# H1DR21.net
KiCad netlist of a schematic drawn in EAGLE
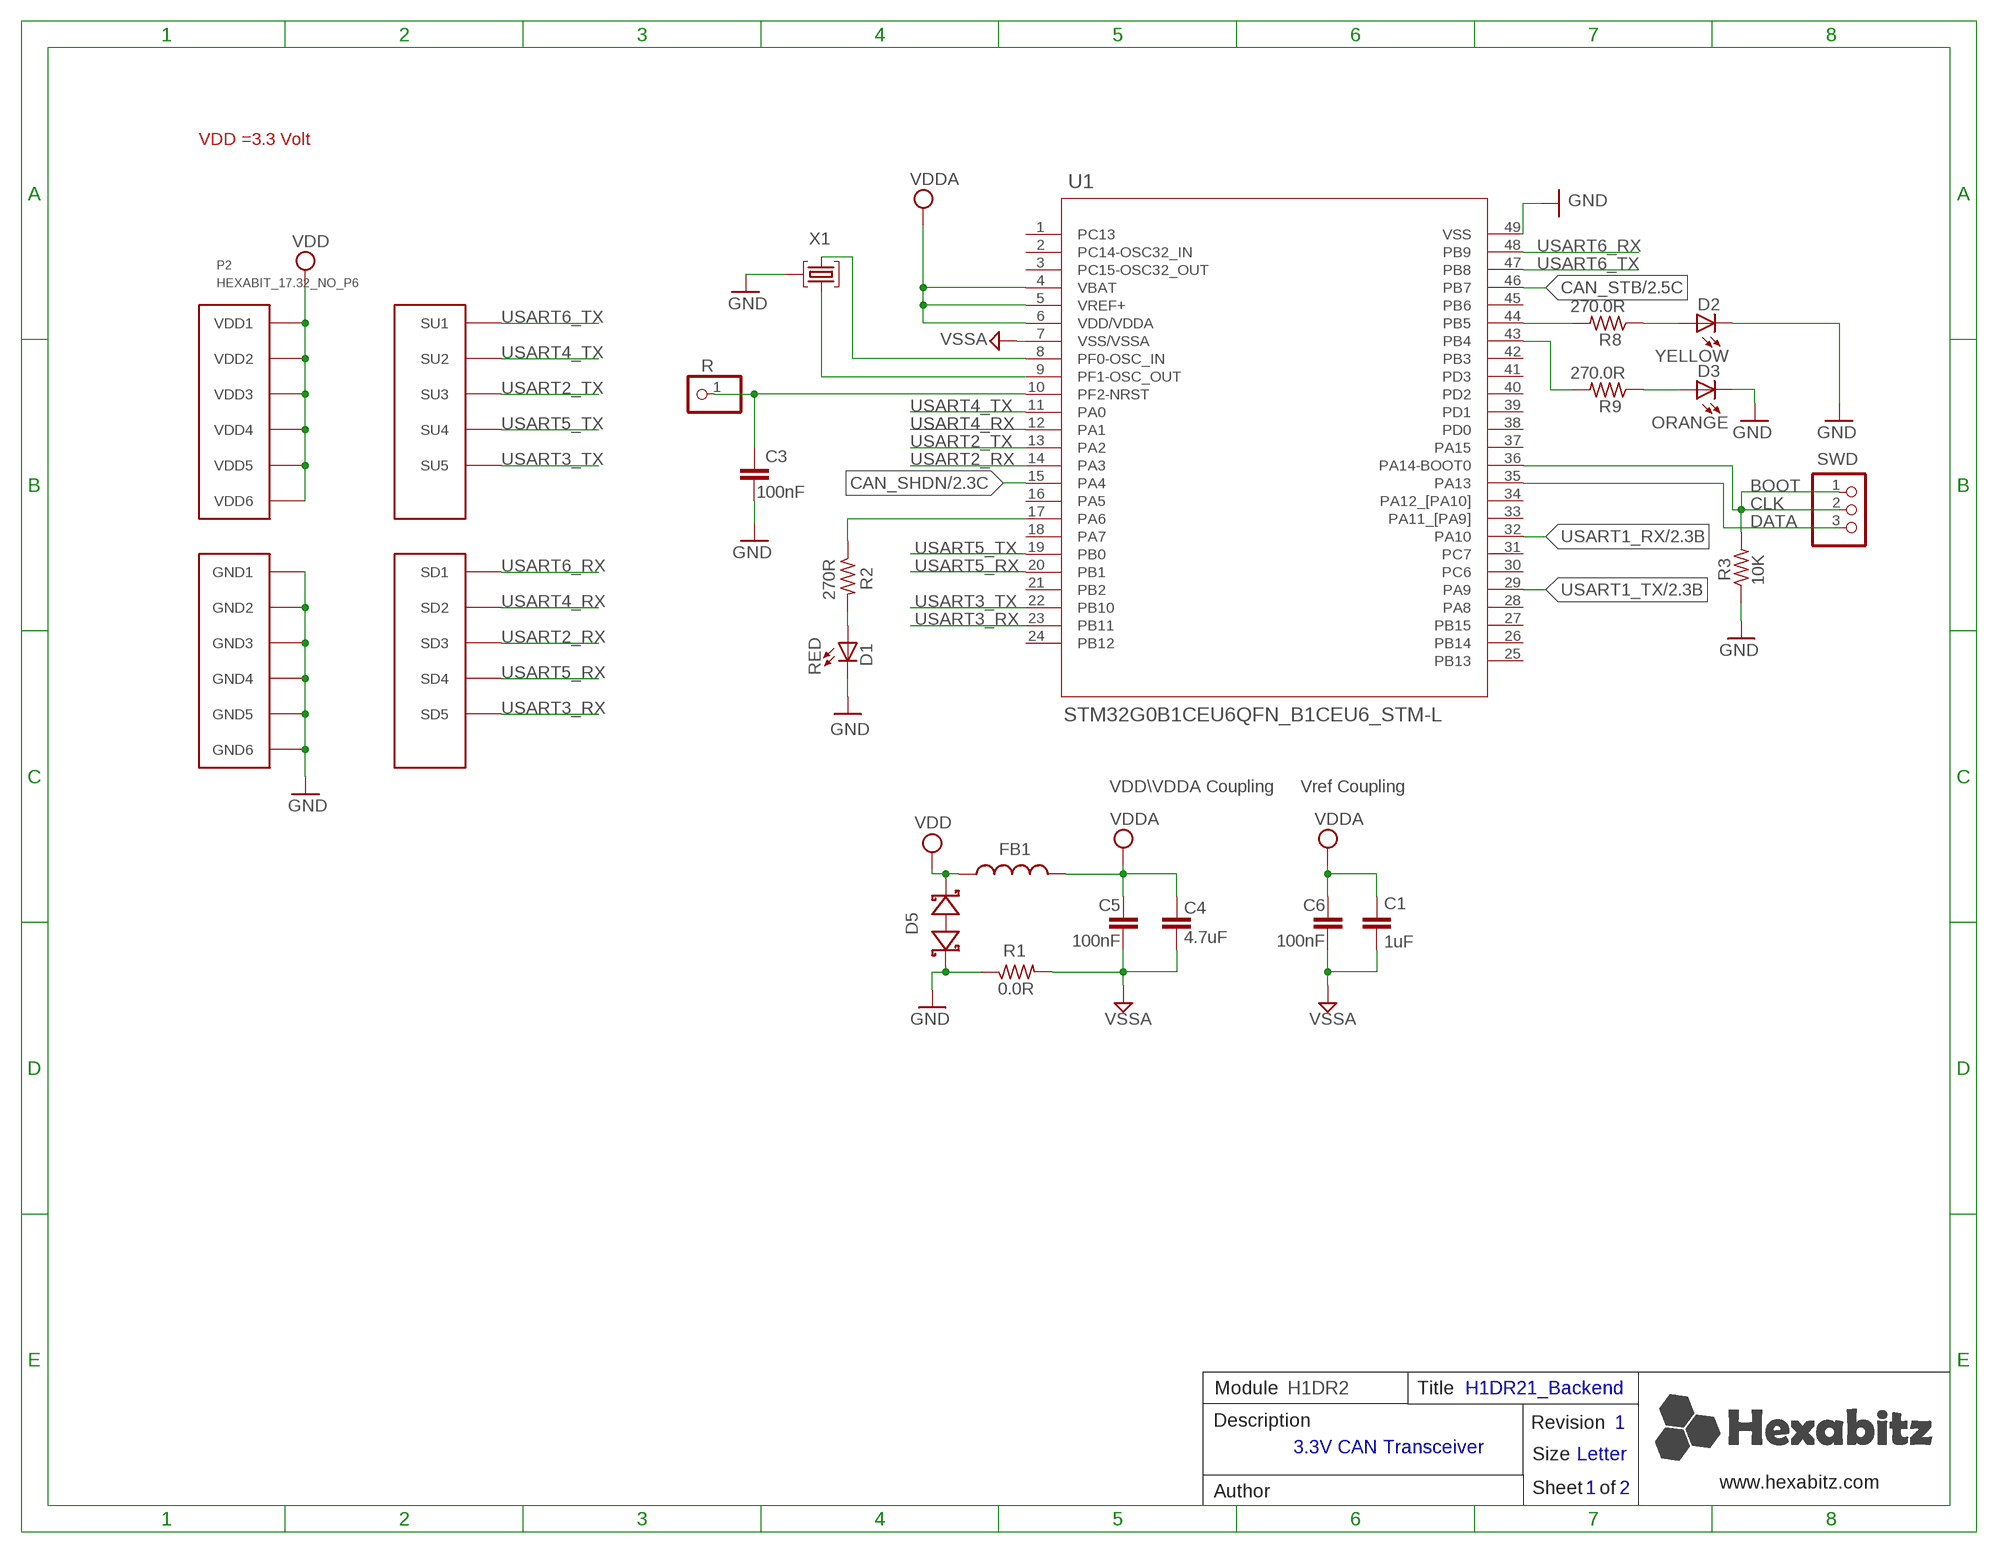
[diagram p0: schematic, sheet 1]
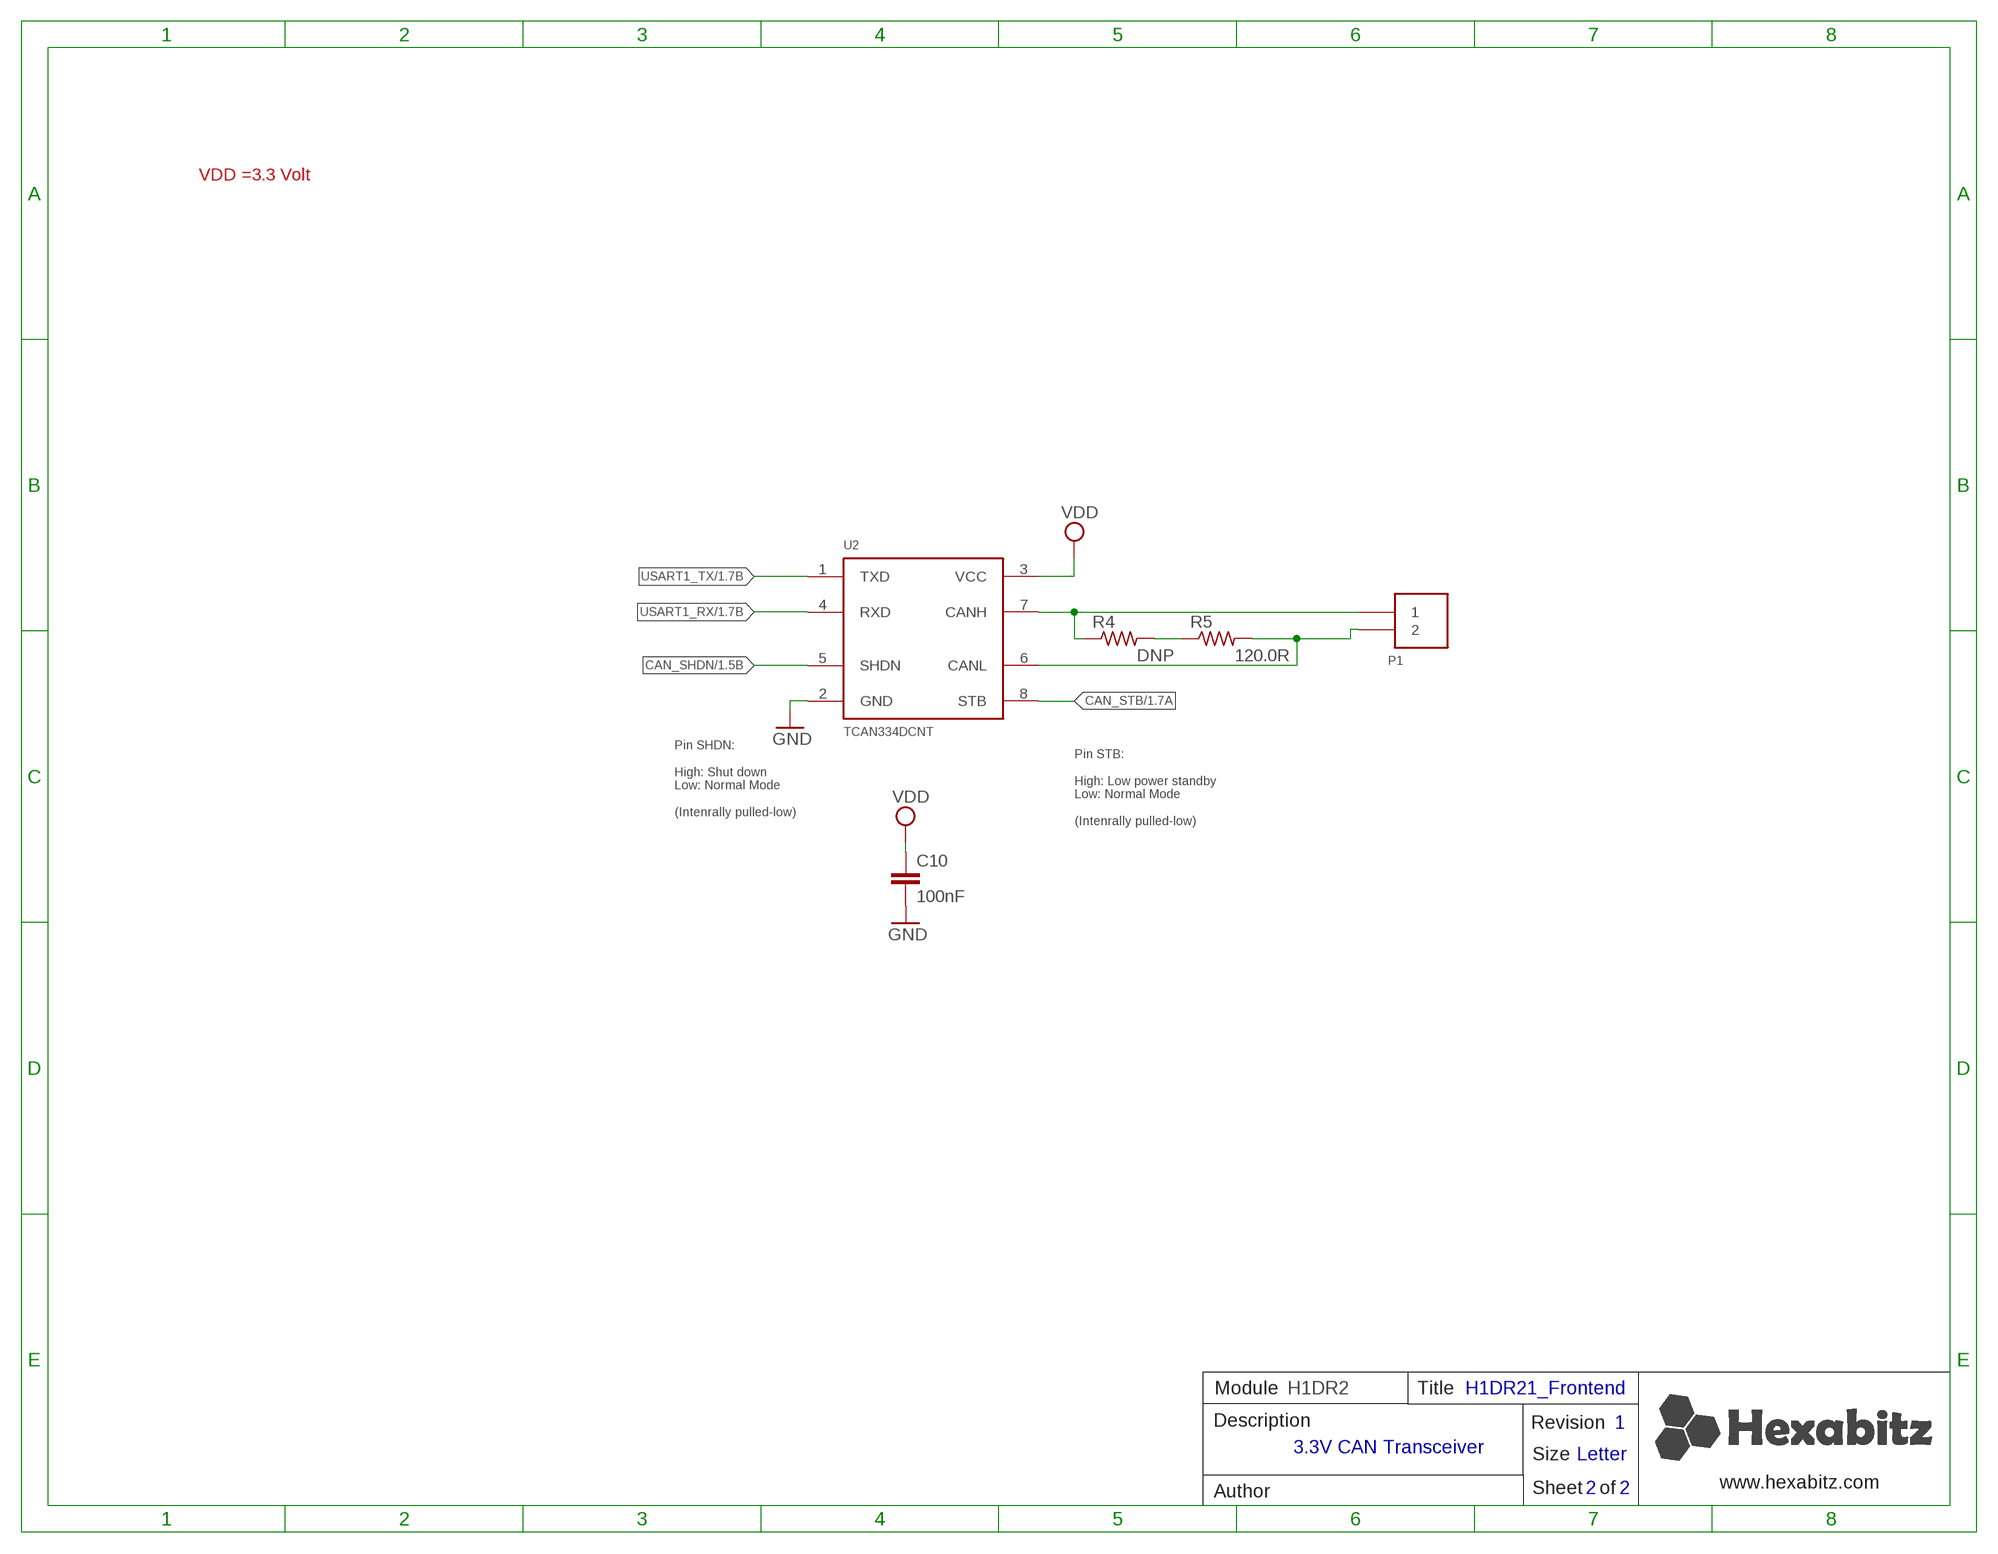
[diagram p1: schematic, sheet 2]

(export (version "E")
  (design (tool "Eeschema 10.0.6"))
  (components
    (comp (ref "C10")
      (value "100nF")
      (footprint "eagle-import:C-0603")
      (fields
        (field (name "CAPACITANCE") "100nF")
        (field (name "MFN") "KEMET")
        (field (name "MPN") "C0603C104K8RACTU")
        (field (name "OCTOPART_URL") "https://octopart.com/c0603c104k8ractu-kemet-145075?r=sp&s=9bS9ASSwSEqMCE9KBEQZ0g")
        (field (name "TOLERANCE") "10%")
        (field (name "VOLTAGE_RATING") "10V")
      )
      (libsource (lib "eagle-import") (part "Hexabitz_C-0603"))
    )
    (comp (ref "P1")
      (value "1546111-2")
      (footprint "eagle-import:1546111-2")
      (libsource (lib "eagle-import") (part "1546111-2"))
    )
    (comp (ref "R4")
      (value "DNP")
      (footprint "eagle-import:R-0603")
      (fields
        (field (name "MFN") "Yageo")
        (field (name "MPN") "RC0603JR-070RL")
        (field (name "OCTOPART_URL") "https://octopart.com/search?q=RC0603JR-070RL")
        (field (name "RESISTANCE") "0.0 Ohm")
      )
      (libsource (lib "eagle-import") (part "Hexabitz_R-0603"))
    )
    (comp (ref "R5")
      (value "120.0R")
      (footprint "eagle-import:R-0603")
      (fields
        (field (name "MFN") "Yageo")
        (field (name "MPN") "AC0603FR-07120RL")
        (field (name "OCTOPART_URL") "https://octopart.com/search?q=AC0603FR-07120RL&start=0")
        (field (name "RESISTANCE") "120.0 Ohm")
        (field (name "TOLERANCE") "1%")
      )
      (libsource (lib "eagle-import") (part "Hexabitz_R-0603"))
    )
    (comp (ref "U2")
      (value "TCAN334DCNT")
      (footprint "eagle-import:TCAN334DCNT")
      (libsource (lib "eagle-import") (part "TCAN334DCNT"))
    )
    (comp (ref "C1")
      (value "1uF")
      (footprint "eagle-import:C-0805")
      (libsource (lib "eagle-import") (part "C-0805"))
    )
    (comp (ref "C3")
      (value "100nF")
      (footprint "eagle-import:C-0603")
      (libsource (lib "eagle-import") (part "C-0603"))
    )
    (comp (ref "C4")
      (value "4.7uF")
      (footprint "eagle-import:C-0805")
      (libsource (lib "eagle-import") (part "C-0805"))
    )
    (comp (ref "C5")
      (value "100nF")
      (footprint "eagle-import:C-0603")
      (libsource (lib "eagle-import") (part "C-0603"))
    )
    (comp (ref "C6")
      (value "100nF")
      (footprint "eagle-import:C-0603")
      (libsource (lib "eagle-import") (part "C-0603"))
    )
    (comp (ref "D1")
      (value "RED")
      (footprint "eagle-import:VLMS1300-GS08")
      (fields
        (field (name "MPN") "VLMS1300-GS08")
        (field (name "MFN") "Vishay")
        (field (name "MPN_1") "VLMS1300-GS08")
        (field (name "OCTOPART_URL") "https://octopart.com/vlms1300-gs08-vishay-21709201?r=sp&s=_gcP4_q8T1SC6PJQPTQ9yA")
      )
      (libsource (lib "eagle-import") (part "VLMS1300-GS08"))
    )
    (comp (ref "D2")
      (value "YELLOW")
      (footprint "eagle-import:VLMS1300-GS08")
      (fields
        (field (name "MPN") "VLMS1300-GS08")
        (field (name "OCTOPART_URL") "https://octopart.com/vlms1300-gs08-vishay-21709201?r=sp&s=_gcP4_q8T1SC6PJQPTQ9yA")
      )
      (libsource (lib "eagle-import") (part "VLMS1300-GS08"))
    )
    (comp (ref "D3")
      (value "ORANGE")
      (footprint "eagle-import:VLMS1300-GS08")
      (fields
        (field (name "MPN") "VLMS1300-GS08")
        (field (name "OCTOPART_URL") "https://octopart.com/vlms1300-gs08-vishay-21709201?r=sp&s=_gcP4_q8T1SC6PJQPTQ9yA")
      )
      (libsource (lib "eagle-import") (part "VLMS1300-GS08"))
    )
    (comp (ref "D5")
      (value "BOURNS_CDSOD323-T03SCBOURNS_CDSOD323-T03SC_0_0")
      (footprint "eagle-import:BOURNS_CDSOD323-T03SC_0")
      (fields (field (name "MPN") "CDSOD323-T03SC"))
      (libsource (lib "eagle-import") (part "BOURNS_CDSOD323-T03SCBOURNS_CDSOD323-T03SC_0_0"))
    )
    (comp (ref "FB1")
      (value "FB-TDK_MMZ1608Y300B")
      (footprint "eagle-import:FB-0603")
      (fields
        (field (name "MFN") "TDK ")
        (field (name "MPN") "MMZ1608Y300B")
        (field (name "OCTOPART_URL") "https://octopart.com/mmz1608y300b-tdk-368280?r=sp&s=cd9_2ZEqQ9q9UNBuQgHAiA")
      )
      (libsource (lib "eagle-import") (part "FB-0603"))
    )
    (comp (ref "P2")
      (value "HEXABIT_17.32_NO_P6")
      (footprint "eagle-import:HEXABIT_17.32_NO_P6")
      (libsource (lib "eagle-import") (part "HEXABIT_?_NO_P617.32"))
    )
    (comp (ref "R")
      (value "R")
      (footprint "eagle-import:1X01")
      (fields (field (name "MPN") "87227-1"))
      (libsource (lib "eagle-import") (part "PINHD-1X1"))
    )
    (comp (ref "R1")
      (value "0.0R")
      (footprint "eagle-import:R-0603")
      (fields
        (field (name "MFN") "Yageo")
        (field (name "MPN") "RC0603JR-070RL")
        (field (name "OCTOPART_URL") "https://octopart.com/rc0603jr-070rl-yageo-1241539?r=sp&s=X2NteqRjRNWrnx42Y0aliA")
        (field (name "RESISTANCE") "0.0 Ohm")
      )
      (libsource (lib "eagle-import") (part "R-0603"))
    )
    (comp (ref "R2")
      (value "270R")
      (footprint "eagle-import:R-0603")
      (libsource (lib "eagle-import") (part "R-0603"))
    )
    (comp (ref "R3")
      (value "10K")
      (footprint "eagle-import:R-0603")
      (libsource (lib "eagle-import") (part "R-0603"))
    )
    (comp (ref "R8")
      (value "270.0R")
      (footprint "eagle-import:R-0603")
      (libsource (lib "eagle-import") (part "R-0603"))
    )
    (comp (ref "R9")
      (value "270.0R")
      (footprint "eagle-import:R-0603")
      (libsource (lib "eagle-import") (part "R-0603"))
    )
    (comp (ref "SWD")
      (value "PINHD-1X3")
      (footprint "eagle-import:1X03")
      (libsource (lib "eagle-import") (part "PINHD-1X3"))
    )
    (comp (ref "U1")
      (value "STM32G0B1CEU6QFN_B1CEU6_STM-L")
      (footprint "eagle-import:QFN_B1CEU6_STM-L")
      (fields
        (field (name "MANUFACTURER_PART_NUMBER") "STM32G0B1CEU6")
        (field (name "SPICEPREFIX") "X")
        (field (name "COPYRIGHT") "Copyright (C) 2021 Ultra Librarian. All rights reserved.")
      )
      (libsource (lib "eagle-import") (part "STM32G0B1CEU6QFN_B1CEU6_STM-L"))
    )
    (comp (ref "X1")
      (value "XTALL_CSTCE8M00G52")
      (footprint "eagle-import:XTALL_CSTCE8M00G52")
      (fields (field (name "MPN") "CSTCE8M00G52Z-R0"))
      (libsource (lib "eagle-import") (part "XTALL_CSTCE8M00G52"))
    )
  )
  (nets
    (net (code "1") (name "CAN_SHDN") (class "Default")
      (node (ref "U1") (pin "15") (pinfunction "PA4_15") (pintype "bidirectional"))
      (node (ref "U2") (pin "5") (pinfunction "SHDN_5") (pintype "bidirectional"))
    )
    (net (code "2") (name "CAN_STB") (class "Default")
      (node (ref "U1") (pin "46") (pinfunction "PB7_46") (pintype "bidirectional"))
      (node (ref "U2") (pin "8") (pinfunction "STB_8") (pintype "bidirectional"))
    )
    (net (code "3") (name "CLK") (class "Default")
      (node (ref "R3") (pin "2") (pinfunction "2_2") (pintype "passive"))
      (node (ref "SWD") (pin "1") (pinfunction "1_1") (pintype "passive"))
      (node (ref "SWD") (pin "2") (pinfunction "2_2") (pintype "passive"))
      (node (ref "U1") (pin "36") (pinfunction "PA14-BOOT0_36") (pintype "bidirectional"))
    )
    (net (code "4") (name "DATA") (class "Default")
      (node (ref "SWD") (pin "3") (pinfunction "3_3") (pintype "passive"))
      (node (ref "U1") (pin "35") (pinfunction "PA13_35") (pintype "bidirectional"))
    )
    (net (code "5") (name "GND") (class "Default")
      (node (ref "C10") (pin "2") (pinfunction "2_2") (pintype "passive"))
      (node (ref "C3") (pin "2") (pinfunction "2_2") (pintype "passive"))
      (node (ref "D1") (pin "C") (pinfunction "C_C") (pintype "passive"))
      (node (ref "D2") (pin "C") (pinfunction "C_C") (pintype "passive"))
      (node (ref "D3") (pin "C") (pinfunction "C_C") (pintype "passive"))
      (node (ref "D5") (pin "1") (pinfunction "A_1") (pintype "passive"))
      (node (ref "P2") (pin "PAD_PD10") (pinfunction "GND4_PAD_PD10") (pintype "power_in"))
      (node (ref "P2") (pin "PAD_PD11") (pinfunction "GND5_PAD_PD11") (pintype "power_in"))
      (node (ref "P2") (pin "PAD_PD12") (pinfunction "GND6_PAD_PD12") (pintype "power_in"))
      (node (ref "P2") (pin "PAD_PD7") (pinfunction "GND1_PAD_PD7") (pintype "power_in"))
      (node (ref "P2") (pin "PAD_PD8") (pinfunction "GND2_PAD_PD8") (pintype "power_in"))
      (node (ref "P2") (pin "PAD_PD9") (pinfunction "GND3_PAD_PD9") (pintype "power_in"))
      (node (ref "R1") (pin "1") (pinfunction "1_1") (pintype "passive"))
      (node (ref "R3") (pin "1") (pinfunction "1_1") (pintype "passive"))
      (node (ref "U1") (pin "49") (pinfunction "VSS_49") (pintype "passive"))
      (node (ref "U2") (pin "2") (pinfunction "GND_2") (pintype "bidirectional"))
      (node (ref "X1") (pin "P$2") (pinfunction "2_P$2") (pintype "passive"))
    )
    (net (code "6") (name "Net-(D1-PadA)") (class "Default")
      (node (ref "D1") (pin "A") (pinfunction "A_A") (pintype "passive"))
      (node (ref "R2") (pin "2") (pinfunction "2_2") (pintype "passive"))
    )
    (net (code "7") (name "Net-(D2-PadA)") (class "Default")
      (node (ref "D2") (pin "A") (pinfunction "A_A") (pintype "passive"))
      (node (ref "R8") (pin "1") (pinfunction "1_1") (pintype "passive"))
    )
    (net (code "8") (name "Net-(D3-PadA)") (class "Default")
      (node (ref "D3") (pin "A") (pinfunction "A_A") (pintype "passive"))
      (node (ref "R9") (pin "1") (pinfunction "1_1") (pintype "passive"))
    )
    (net (code "9") (name "Net-(R4-Pad2)") (class "Default")
      (node (ref "R4") (pin "2") (pinfunction "2_2") (pintype "passive"))
      (node (ref "R5") (pin "1") (pinfunction "1_1") (pintype "passive"))
    )
    (net (code "10") (name "Net-(U1-PA6)") (class "Default")
      (node (ref "R2") (pin "1") (pinfunction "1_1") (pintype "passive"))
      (node (ref "U1") (pin "17") (pinfunction "PA6_17") (pintype "bidirectional"))
    )
    (net (code "11") (name "Net-(U1-PB4)") (class "Default")
      (node (ref "R9") (pin "2") (pinfunction "2_2") (pintype "passive"))
      (node (ref "U1") (pin "43") (pinfunction "PB4_43") (pintype "bidirectional"))
    )
    (net (code "12") (name "Net-(U1-PB5)") (class "Default")
      (node (ref "R8") (pin "2") (pinfunction "2_2") (pintype "passive"))
      (node (ref "U1") (pin "44") (pinfunction "PB5_44") (pintype "bidirectional"))
    )
    (net (code "13") (name "Net-(U1-PF0-OSC_IN)") (class "Default")
      (node (ref "U1") (pin "8") (pinfunction "PF0-OSC_IN_8") (pintype "bidirectional"))
      (node (ref "X1") (pin "P$3") (pinfunction "3_P$3") (pintype "passive"))
    )
    (net (code "14") (name "Net-(U1-PF1-OSC_OUT)") (class "Default")
      (node (ref "U1") (pin "9") (pinfunction "PF1-OSC_OUT_9") (pintype "output"))
      (node (ref "X1") (pin "P$1") (pinfunction "1_P$1") (pintype "passive"))
    )
    (net (code "15") (name "Net-(U1-PF2-NRST)") (class "Default")
      (node (ref "C3") (pin "1") (pinfunction "1_1") (pintype "passive"))
      (node (ref "R") (pin "1") (pinfunction "1_1") (pintype "passive"))
      (node (ref "U1") (pin "10") (pinfunction "PF2-NRST_10") (pintype "bidirectional"))
    )
    (net (code "16") (name "Net-(U2-CANH)") (class "Default")
      (node (ref "P1") (pin "1") (pinfunction "1_1") (pintype "power_in"))
      (node (ref "R4") (pin "1") (pinfunction "1_1") (pintype "passive"))
      (node (ref "U2") (pin "7") (pinfunction "CANH_7") (pintype "bidirectional"))
    )
    (net (code "17") (name "Net-(U2-CANL)") (class "Default")
      (node (ref "P1") (pin "2") (pinfunction "2_2") (pintype "power_in"))
      (node (ref "R5") (pin "2") (pinfunction "2_2") (pintype "passive"))
      (node (ref "U2") (pin "6") (pinfunction "CANL_6") (pintype "bidirectional"))
    )
    (net (code "18") (name "USART1_RX") (class "Default")
      (node (ref "U1") (pin "32") (pinfunction "PA10_32") (pintype "bidirectional"))
      (node (ref "U2") (pin "4") (pinfunction "RXD_4") (pintype "bidirectional"))
    )
    (net (code "19") (name "USART1_TX") (class "Default")
      (node (ref "U1") (pin "29") (pinfunction "PA9_29") (pintype "bidirectional"))
      (node (ref "U2") (pin "1") (pinfunction "TXD_1") (pintype "bidirectional"))
    )
    (net (code "20") (name "USART2_RX") (class "Default")
      (node (ref "P2") (pin "PAD_PD3") (pinfunction "SD3_PAD_PD3") (pintype "bidirectional"))
      (node (ref "U1") (pin "14") (pinfunction "PA3_14") (pintype "bidirectional"))
    )
    (net (code "21") (name "USART2_TX") (class "Default")
      (node (ref "P2") (pin "PAD_PU3") (pinfunction "SU3_PAD_PU3") (pintype "bidirectional"))
      (node (ref "U1") (pin "13") (pinfunction "PA2_13") (pintype "bidirectional"))
    )
    (net (code "22") (name "USART3_RX") (class "Default")
      (node (ref "P2") (pin "PAD_PD5") (pinfunction "SD5_PAD_PD5") (pintype "bidirectional"))
      (node (ref "U1") (pin "23") (pinfunction "PB11_23") (pintype "bidirectional"))
    )
    (net (code "23") (name "USART3_TX") (class "Default")
      (node (ref "P2") (pin "PAD_PU5") (pinfunction "SU5_PAD_PU5") (pintype "bidirectional"))
      (node (ref "U1") (pin "22") (pinfunction "PB10_22") (pintype "bidirectional"))
    )
    (net (code "24") (name "USART4_RX") (class "Default")
      (node (ref "P2") (pin "PAD_PD2") (pinfunction "SD2_PAD_PD2") (pintype "bidirectional"))
      (node (ref "U1") (pin "12") (pinfunction "PA1_12") (pintype "bidirectional"))
    )
    (net (code "25") (name "USART4_TX") (class "Default")
      (node (ref "P2") (pin "PAD_PU2") (pinfunction "SU2_PAD_PU2") (pintype "bidirectional"))
      (node (ref "U1") (pin "11") (pinfunction "PA0_11") (pintype "bidirectional"))
    )
    (net (code "26") (name "USART5_RX") (class "Default")
      (node (ref "P2") (pin "PAD_PD4") (pinfunction "SD4_PAD_PD4") (pintype "bidirectional"))
      (node (ref "U1") (pin "20") (pinfunction "PB1_20") (pintype "bidirectional"))
    )
    (net (code "27") (name "USART5_TX") (class "Default")
      (node (ref "P2") (pin "PAD_PU4") (pinfunction "SU4_PAD_PU4") (pintype "bidirectional"))
      (node (ref "U1") (pin "19") (pinfunction "PB0_19") (pintype "bidirectional"))
    )
    (net (code "28") (name "USART6_RX") (class "Default")
      (node (ref "P2") (pin "PAD_PD1") (pinfunction "SD1_PAD_PD1") (pintype "bidirectional"))
      (node (ref "U1") (pin "48") (pinfunction "PB9_48") (pintype "bidirectional"))
    )
    (net (code "29") (name "USART6_TX") (class "Default")
      (node (ref "P2") (pin "PAD_PU1") (pinfunction "SU1_PAD_PU1") (pintype "bidirectional"))
      (node (ref "U1") (pin "47") (pinfunction "PB8_47") (pintype "bidirectional"))
    )
    (net (code "30") (name "VDD") (class "Default")
      (node (ref "C10") (pin "1") (pinfunction "1_1") (pintype "passive"))
      (node (ref "D5") (pin "2") (pinfunction "C_2") (pintype "passive"))
      (node (ref "FB1") (pin "2") (pinfunction "2_2") (pintype "passive"))
      (node (ref "P2") (pin "PAD_PU10") (pinfunction "VDD4_PAD_PU10") (pintype "power_in"))
      (node (ref "P2") (pin "PAD_PU11") (pinfunction "VDD5_PAD_PU11") (pintype "power_in"))
      (node (ref "P2") (pin "PAD_PU12") (pinfunction "VDD6_PAD_PU12") (pintype "power_in"))
      (node (ref "P2") (pin "PAD_PU7") (pinfunction "VDD1_PAD_PU7") (pintype "power_in"))
      (node (ref "P2") (pin "PAD_PU8") (pinfunction "VDD2_PAD_PU8") (pintype "power_in"))
      (node (ref "P2") (pin "PAD_PU9") (pinfunction "VDD3_PAD_PU9") (pintype "power_in"))
      (node (ref "U2") (pin "3") (pinfunction "VCC_3") (pintype "bidirectional"))
    )
    (net (code "31") (name "VDDA") (class "Default")
      (node (ref "C1") (pin "1") (pinfunction "1_1") (pintype "passive"))
      (node (ref "C4") (pin "1") (pinfunction "1_1") (pintype "passive"))
      (node (ref "C5") (pin "1") (pinfunction "1_1") (pintype "passive"))
      (node (ref "C6") (pin "1") (pinfunction "1_1") (pintype "passive"))
      (node (ref "FB1") (pin "1") (pinfunction "1_1") (pintype "passive"))
      (node (ref "U1") (pin "4") (pinfunction "VBAT_4") (pintype "passive"))
      (node (ref "U1") (pin "5") (pinfunction "VREF+_5") (pintype "power_in"))
      (node (ref "U1") (pin "6") (pinfunction "VDD/VDDA_6") (pintype "power_in"))
    )
    (net (code "32") (name "VSSA") (class "Default")
      (node (ref "C1") (pin "2") (pinfunction "2_2") (pintype "passive"))
      (node (ref "C4") (pin "2") (pinfunction "2_2") (pintype "passive"))
      (node (ref "C5") (pin "2") (pinfunction "2_2") (pintype "passive"))
      (node (ref "C6") (pin "2") (pinfunction "2_2") (pintype "passive"))
      (node (ref "R1") (pin "2") (pinfunction "2_2") (pintype "passive"))
      (node (ref "U1") (pin "7") (pinfunction "VSS/VSSA_7") (pintype "passive"))
    )
    (net (code "33") (name "unconnected-(U1-PA5-Pad16)") (class "Default")
      (node (ref "U1") (pin "16") (pinfunction "PA5_16") (pintype "bidirectional"))
    )
    (net (code "34") (name "unconnected-(U1-PA7-Pad18)") (class "Default")
      (node (ref "U1") (pin "18") (pinfunction "PA7_18") (pintype "bidirectional"))
    )
    (net (code "35") (name "unconnected-(U1-PA8-Pad28)") (class "Default")
      (node (ref "U1") (pin "28") (pinfunction "PA8_28") (pintype "bidirectional"))
    )
    (net (code "36") (name "unconnected-(U1-PA11_[PA9]-Pad33)") (class "Default")
      (node (ref "U1") (pin "33") (pinfunction "PA11_[PA9]_33") (pintype "bidirectional"))
    )
    (net (code "37") (name "unconnected-(U1-PA12_[PA10]-Pad34)") (class "Default")
      (node (ref "U1") (pin "34") (pinfunction "PA12_[PA10]_34") (pintype "bidirectional"))
    )
    (net (code "38") (name "unconnected-(U1-PA15-Pad37)") (class "Default")
      (node (ref "U1") (pin "37") (pinfunction "PA15_37") (pintype "bidirectional"))
    )
    (net (code "39") (name "unconnected-(U1-PB2-Pad21)") (class "Default")
      (node (ref "U1") (pin "21") (pinfunction "PB2_21") (pintype "bidirectional"))
    )
    (net (code "40") (name "unconnected-(U1-PB3-Pad42)") (class "Default")
      (node (ref "U1") (pin "42") (pinfunction "PB3_42") (pintype "bidirectional"))
    )
    (net (code "41") (name "unconnected-(U1-PB6-Pad45)") (class "Default")
      (node (ref "U1") (pin "45") (pinfunction "PB6_45") (pintype "bidirectional"))
    )
    (net (code "42") (name "unconnected-(U1-PB12-Pad24)") (class "Default")
      (node (ref "U1") (pin "24") (pinfunction "PB12_24") (pintype "bidirectional"))
    )
    (net (code "43") (name "unconnected-(U1-PB13-Pad25)") (class "Default")
      (node (ref "U1") (pin "25") (pinfunction "PB13_25") (pintype "bidirectional"))
    )
    (net (code "44") (name "unconnected-(U1-PB14-Pad26)") (class "Default")
      (node (ref "U1") (pin "26") (pinfunction "PB14_26") (pintype "bidirectional"))
    )
    (net (code "45") (name "unconnected-(U1-PB15-Pad27)") (class "Default")
      (node (ref "U1") (pin "27") (pinfunction "PB15_27") (pintype "bidirectional"))
    )
    (net (code "46") (name "unconnected-(U1-PC6-Pad30)") (class "Default")
      (node (ref "U1") (pin "30") (pinfunction "PC6_30") (pintype "bidirectional"))
    )
    (net (code "47") (name "unconnected-(U1-PC7-Pad31)") (class "Default")
      (node (ref "U1") (pin "31") (pinfunction "PC7_31") (pintype "bidirectional"))
    )
    (net (code "48") (name "unconnected-(U1-PC13-Pad1)") (class "Default")
      (node (ref "U1") (pin "1") (pinfunction "PC13_1") (pintype "bidirectional"))
    )
    (net (code "49") (name "unconnected-(U1-PC14-OSC32_IN-Pad2)") (class "Default")
      (node (ref "U1") (pin "2") (pinfunction "PC14-OSC32_IN_2") (pintype "bidirectional"))
    )
    (net (code "50") (name "unconnected-(U1-PC15-OSC32_OUT-Pad3)") (class "Default")
      (node (ref "U1") (pin "3") (pinfunction "PC15-OSC32_OUT_3") (pintype "output"))
    )
    (net (code "51") (name "unconnected-(U1-PD0-Pad38)") (class "Default")
      (node (ref "U1") (pin "38") (pinfunction "PD0_38") (pintype "bidirectional"))
    )
    (net (code "52") (name "unconnected-(U1-PD1-Pad39)") (class "Default")
      (node (ref "U1") (pin "39") (pinfunction "PD1_39") (pintype "bidirectional"))
    )
    (net (code "53") (name "unconnected-(U1-PD2-Pad40)") (class "Default")
      (node (ref "U1") (pin "40") (pinfunction "PD2_40") (pintype "bidirectional"))
    )
    (net (code "54") (name "unconnected-(U1-PD3-Pad41)") (class "Default")
      (node (ref "U1") (pin "41") (pinfunction "PD3_41") (pintype "bidirectional"))
    )
  )
)
